# Aurel-super-regen-receiver-ASR2.net
KiCad netlist of a schematic drawn in EAGLE
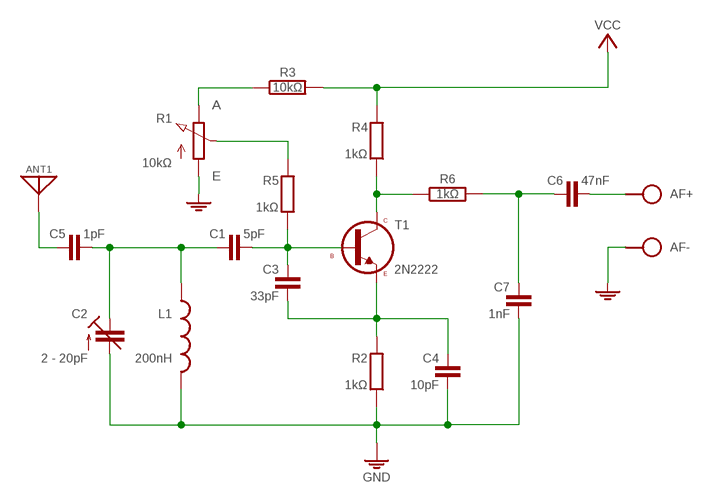
[diagram p0: schematic, sheet 1]

(export (version "E")
  (design (tool "Eeschema 10.0.6"))
  (components
    (comp (ref "AF")
      (value "SPAD+-+-")
      (footprint "eagle-import:SPAD+-")
      (libsource (lib "eagle-import") (part "SPAD+-+-"))
    )
    (comp (ref "ANT1")
      (value "ANT")
      (footprint "eagle-import:SPAD")
      (libsource (lib "eagle-import") (part "ANT"))
    )
    (comp (ref "C1")
      (value "5pF")
      (footprint "eagle-import:C025-015X024")
      (libsource (lib "eagle-import") (part "C-H025-015X024"))
    )
    (comp (ref "C2")
      (value "2 - 20pF")
      (footprint "eagle-import:TRIM-2222-808")
      (libsource (lib "eagle-import") (part "C-TR-PH201272222-808-2PINB"))
    )
    (comp (ref "C3")
      (value "33pF")
      (footprint "eagle-import:C025-015X024")
      (libsource (lib "eagle-import") (part "C025-015X024"))
    )
    (comp (ref "C4")
      (value "10pF")
      (footprint "eagle-import:C025-015X024")
      (libsource (lib "eagle-import") (part "C025-015X024"))
    )
    (comp (ref "C5")
      (value "1pF")
      (footprint "eagle-import:C025-015X024")
      (libsource (lib "eagle-import") (part "C-H025-015X024"))
    )
    (comp (ref "C6")
      (value "47nF")
      (footprint "eagle-import:C050-020X044")
      (libsource (lib "eagle-import") (part "C-H050-020X044"))
    )
    (comp (ref "C7")
      (value "1nF")
      (footprint "eagle-import:C050-020X044_V")
      (libsource (lib "eagle-import") (part "C050-020X044/V"))
    )
    (comp (ref "L1")
      (value "200nH")
      (footprint "eagle-import:L-04_7-V")
      (libsource (lib "eagle-import") (part "L04/7-V"))
    )
    (comp (ref "R1")
      (value "10kΩ")
      (footprint "eagle-import:POT")
      (libsource (lib "eagle-import") (part "POT"))
    )
    (comp (ref "R2")
      (value "1kΩ")
      (footprint "eagle-import:0204_10-V")
      (libsource (lib "eagle-import") (part "R0204/10-V"))
    )
    (comp (ref "R3")
      (value "10kΩ")
      (footprint "eagle-import:0204_10")
      (libsource (lib "eagle-import") (part "R-H0204/10"))
    )
    (comp (ref "R4")
      (value "1kΩ")
      (footprint "eagle-import:0204_10-V")
      (libsource (lib "eagle-import") (part "R0204/10-V"))
    )
    (comp (ref "R5")
      (value "1kΩ")
      (footprint "eagle-import:0204_10-V")
      (libsource (lib "eagle-import") (part "R0204/10-V"))
    )
    (comp (ref "R6")
      (value "1kΩ")
      (footprint "eagle-import:0204_10")
      (libsource (lib "eagle-import") (part "R-H0204/10"))
    )
    (comp (ref "S2")
      (value "VCC_GNDPWR-L")
      (footprint "eagle-import:PWR-L")
      (libsource (lib "eagle-import") (part "VCC_GNDPWR-L"))
    )
    (comp (ref "T1")
      (value "2N2222")
      (footprint "eagle-import:TO92-EBC")
      (libsource (lib "eagle-import") (part "2N2222"))
    )
  )
  (nets
    (net (code "1") (name "GND") (class "Default")
      (node (ref "AF") (pin "1") (pinfunction "P$1_1") (pintype "passive"))
      (node (ref "C2") (pin "2") (pinfunction "A_2") (pintype "passive"))
      (node (ref "C4") (pin "2") (pinfunction "2_2") (pintype "passive"))
      (node (ref "C7") (pin "2") (pinfunction "2_2") (pintype "passive"))
      (node (ref "L1") (pin "2") (pinfunction "2_2") (pintype "passive"))
      (node (ref "R1") (pin "A") (pinfunction "A_A") (pintype "passive"))
      (node (ref "R2") (pin "2") (pinfunction "1_2") (pintype "passive"))
      (node (ref "S2") (pin "1") (pinfunction "GND_1") (pintype "power_in"))
    )
    (net (code "2") (name "Net-(AFA-P$1)") (class "Default")
      (node (ref "AF") (pin "2") (pinfunction "P$1_2") (pintype "passive"))
      (node (ref "C6") (pin "2") (pinfunction "2_2") (pintype "passive"))
    )
    (net (code "3") (name "Net-(ANT1-Pad1)") (class "Default")
      (node (ref "ANT1") (pin "1") (pinfunction "1_1") (pintype "output"))
      (node (ref "C5") (pin "1") (pinfunction "1_1") (pintype "passive"))
    )
    (net (code "4") (name "Net-(C2-E)") (class "Default")
      (node (ref "C1") (pin "1") (pinfunction "1_1") (pintype "passive"))
      (node (ref "C2") (pin "3") (pinfunction "E_3") (pintype "passive"))
      (node (ref "C5") (pin "2") (pinfunction "2_2") (pintype "passive"))
      (node (ref "L1") (pin "1") (pinfunction "1_1") (pintype "passive"))
    )
    (net (code "5") (name "Net-(C6-Pad1)") (class "Default")
      (node (ref "C6") (pin "1") (pinfunction "1_1") (pintype "passive"))
      (node (ref "C7") (pin "1") (pinfunction "1_1") (pintype "passive"))
      (node (ref "R6") (pin "2") (pinfunction "2_2") (pintype "passive"))
    )
    (net (code "6") (name "Net-(R1-PadE)") (class "Default")
      (node (ref "R1") (pin "E") (pinfunction "E_E") (pintype "passive"))
      (node (ref "R3") (pin "1") (pinfunction "1_1") (pintype "passive"))
    )
    (net (code "7") (name "Net-(R2-2)") (class "Default")
      (node (ref "C3") (pin "2") (pinfunction "2_2") (pintype "passive"))
      (node (ref "C4") (pin "1") (pinfunction "1_1") (pintype "passive"))
      (node (ref "R2") (pin "1") (pinfunction "2_1") (pintype "passive"))
      (node (ref "T1") (pin "E") (pinfunction "E_E") (pintype "passive"))
    )
    (net (code "8") (name "Net-(R4-1)") (class "Default")
      (node (ref "R4") (pin "2") (pinfunction "1_2") (pintype "passive"))
      (node (ref "R6") (pin "1") (pinfunction "1_1") (pintype "passive"))
      (node (ref "T1") (pin "C") (pinfunction "C_C") (pintype "passive"))
    )
    (net (code "9") (name "Net-(R4-2)") (class "Default")
      (node (ref "R3") (pin "2") (pinfunction "2_2") (pintype "passive"))
      (node (ref "R4") (pin "1") (pinfunction "2_1") (pintype "passive"))
      (node (ref "S2") (pin "2") (pinfunction "VCC_2") (pintype "power_in"))
    )
    (net (code "10") (name "Net-(R5-1)") (class "Default")
      (node (ref "C1") (pin "2") (pinfunction "2_2") (pintype "passive"))
      (node (ref "C3") (pin "1") (pinfunction "1_1") (pintype "passive"))
      (node (ref "R5") (pin "2") (pinfunction "1_2") (pintype "passive"))
      (node (ref "T1") (pin "B") (pinfunction "B_B") (pintype "passive"))
    )
    (net (code "11") (name "Net-(R5-2)") (class "Default")
      (node (ref "R1") (pin "S") (pinfunction "S_S") (pintype "passive"))
      (node (ref "R5") (pin "1") (pinfunction "2_1") (pintype "passive"))
    )
  )
)
